# 7-seg_x_8-digRev2.net
KiCad netlist of a schematic drawn in EAGLE
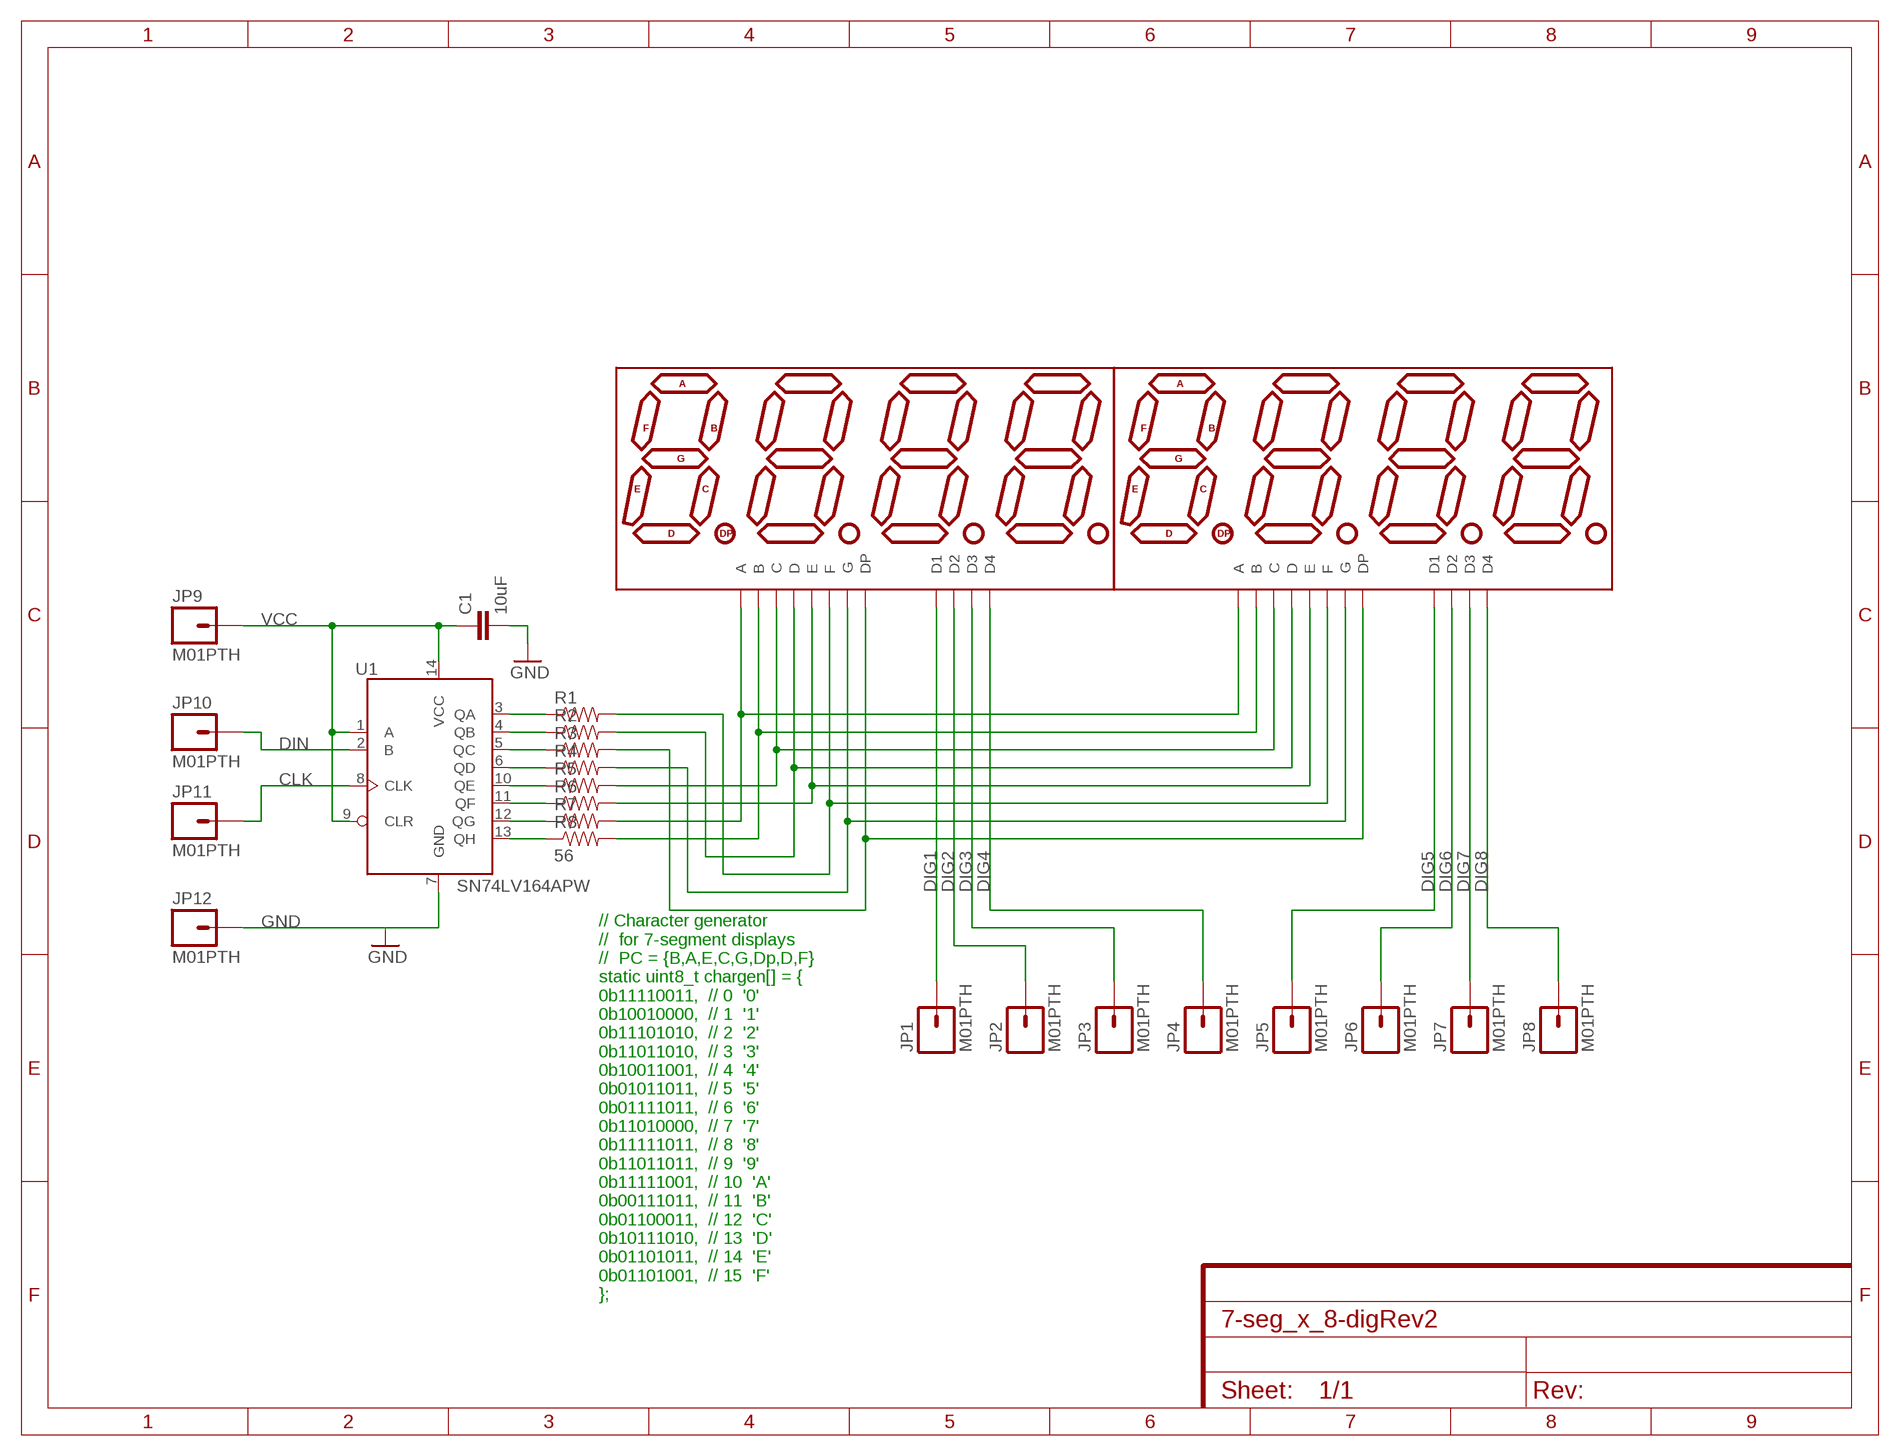
[diagram p0: schematic, sheet 1]

(export (version "E")
  (design (tool "Eeschema 10.0.6"))
  (components
    (comp (ref "C1")
      (value "10uF")
      (footprint "eagle-import:0805")
      (libsource (lib "eagle-import") (part "CAP0805"))
    )
    (comp (ref "FRAME1")
      (value "FRAME_LTR_CU_MARK")
      (footprint "eagle-import:FR-LTR-ON-PCB")
      (fields
        (field (name "CNAME") "C.Schnarel")
        (field (name "CREVISION") "Rev 2")
        (field (name "DESIGNER") "C.Schnarel")
      )
      (libsource (lib "eagle-import") (part "FRAME_LTR_CU_MARK"))
    )
    (comp (ref "JP1")
      (value "M01PTH")
      (footprint "eagle-import:1X01")
      (libsource (lib "eagle-import") (part "M01PTH"))
    )
    (comp (ref "JP2")
      (value "M01PTH")
      (footprint "eagle-import:1X01")
      (libsource (lib "eagle-import") (part "M01PTH"))
    )
    (comp (ref "JP3")
      (value "M01PTH")
      (footprint "eagle-import:1X01")
      (libsource (lib "eagle-import") (part "M01PTH"))
    )
    (comp (ref "JP4")
      (value "M01PTH")
      (footprint "eagle-import:1X01")
      (libsource (lib "eagle-import") (part "M01PTH"))
    )
    (comp (ref "JP5")
      (value "M01PTH")
      (footprint "eagle-import:1X01")
      (libsource (lib "eagle-import") (part "M01PTH"))
    )
    (comp (ref "JP6")
      (value "M01PTH")
      (footprint "eagle-import:1X01")
      (libsource (lib "eagle-import") (part "M01PTH"))
    )
    (comp (ref "JP7")
      (value "M01PTH")
      (footprint "eagle-import:1X01")
      (libsource (lib "eagle-import") (part "M01PTH"))
    )
    (comp (ref "JP8")
      (value "M01PTH")
      (footprint "eagle-import:1X01")
      (libsource (lib "eagle-import") (part "M01PTH"))
    )
    (comp (ref "JP9")
      (value "M01PTH")
      (footprint "eagle-import:1X01")
      (libsource (lib "eagle-import") (part "M01PTH"))
    )
    (comp (ref "JP10")
      (value "M01PTH")
      (footprint "eagle-import:1X01")
      (libsource (lib "eagle-import") (part "M01PTH"))
    )
    (comp (ref "JP11")
      (value "M01PTH")
      (footprint "eagle-import:1X01")
      (libsource (lib "eagle-import") (part "M01PTH"))
    )
    (comp (ref "JP12")
      (value "M01PTH")
      (footprint "eagle-import:1X01")
      (libsource (lib "eagle-import") (part "M01PTH"))
    )
    (comp (ref "R1")
      (value "RESISTOR0805-RES")
      (footprint "eagle-import:0805")
      (libsource (lib "eagle-import") (part "RESISTOR0805-RES"))
    )
    (comp (ref "R2")
      (value "RESISTOR0805-RES")
      (footprint "eagle-import:0805")
      (libsource (lib "eagle-import") (part "RESISTOR0805-RES"))
    )
    (comp (ref "R3")
      (value "RESISTOR0805-RES")
      (footprint "eagle-import:0805")
      (libsource (lib "eagle-import") (part "RESISTOR0805-RES"))
    )
    (comp (ref "R4")
      (value "RESISTOR0805-RES")
      (footprint "eagle-import:0805")
      (libsource (lib "eagle-import") (part "RESISTOR0805-RES"))
    )
    (comp (ref "R5")
      (value "RESISTOR0805-RES")
      (footprint "eagle-import:0805")
      (libsource (lib "eagle-import") (part "RESISTOR0805-RES"))
    )
    (comp (ref "R6")
      (value "RESISTOR0805-RES")
      (footprint "eagle-import:0805")
      (libsource (lib "eagle-import") (part "RESISTOR0805-RES"))
    )
    (comp (ref "R7")
      (value "RESISTOR0805-RES")
      (footprint "eagle-import:0805")
      (libsource (lib "eagle-import") (part "RESISTOR0805-RES"))
    )
    (comp (ref "R8")
      (value "56")
      (footprint "eagle-import:0805")
      (libsource (lib "eagle-import") (part "RESISTOR0805-RES"))
    )
    (comp (ref "U$1")
      (value "HP_DISPLAY")
      (footprint "eagle-import:DIL12")
      (libsource (lib "eagle-import") (part "HP_DISPLAY"))
    )
    (comp (ref "U$2")
      (value "HP_DISPLAY")
      (footprint "eagle-import:DIL12")
      (libsource (lib "eagle-import") (part "HP_DISPLAY"))
    )
    (comp (ref "U1")
      (value "SN74LV164APW")
      (footprint "eagle-import:TSSOP-14(TI)")
      (libsource (lib "eagle-import") (part "SN74LV164APW"))
    )
  )
  (nets
    (net (code "1") (name "/CLK") (class "Default")
      (node (ref "JP11") (pin "1") (pinfunction "1_1") (pintype "passive"))
      (node (ref "U1") (pin "8") (pinfunction "CLK_8") (pintype "input"))
    )
    (net (code "2") (name "/DIG1") (class "Default")
      (node (ref "JP1") (pin "1") (pinfunction "1_1") (pintype "passive"))
      (node (ref "U$1") (pin "1") (pinfunction "D1_1") (pintype "bidirectional"))
    )
    (net (code "3") (name "/DIG2") (class "Default")
      (node (ref "JP2") (pin "1") (pinfunction "1_1") (pintype "passive"))
      (node (ref "U$1") (pin "10") (pinfunction "D2_10") (pintype "bidirectional"))
    )
    (net (code "4") (name "/DIG3") (class "Default")
      (node (ref "JP3") (pin "1") (pinfunction "1_1") (pintype "passive"))
      (node (ref "U$1") (pin "4") (pinfunction "D3_4") (pintype "bidirectional"))
    )
    (net (code "5") (name "/DIG4") (class "Default")
      (node (ref "JP4") (pin "1") (pinfunction "1_1") (pintype "passive"))
      (node (ref "U$1") (pin "6") (pinfunction "D4_6") (pintype "bidirectional"))
    )
    (net (code "6") (name "/DIG5") (class "Default")
      (node (ref "JP5") (pin "1") (pinfunction "1_1") (pintype "passive"))
      (node (ref "U$2") (pin "1") (pinfunction "D1_1") (pintype "bidirectional"))
    )
    (net (code "7") (name "/DIG6") (class "Default")
      (node (ref "JP6") (pin "1") (pinfunction "1_1") (pintype "passive"))
      (node (ref "U$2") (pin "10") (pinfunction "D2_10") (pintype "bidirectional"))
    )
    (net (code "8") (name "/DIG7") (class "Default")
      (node (ref "JP7") (pin "1") (pinfunction "1_1") (pintype "passive"))
      (node (ref "U$2") (pin "4") (pinfunction "D3_4") (pintype "bidirectional"))
    )
    (net (code "9") (name "/DIG8") (class "Default")
      (node (ref "JP8") (pin "1") (pinfunction "1_1") (pintype "passive"))
      (node (ref "U$2") (pin "6") (pinfunction "D4_6") (pintype "bidirectional"))
    )
    (net (code "10") (name "/DIN") (class "Default")
      (node (ref "JP10") (pin "1") (pinfunction "1_1") (pintype "passive"))
      (node (ref "U1") (pin "2") (pinfunction "B_2") (pintype "input"))
    )
    (net (code "11") (name "/VCC") (class "Default")
      (node (ref "C1") (pin "1") (pinfunction "1_1") (pintype "passive"))
      (node (ref "JP9") (pin "1") (pinfunction "1_1") (pintype "passive"))
      (node (ref "U1") (pin "1") (pinfunction "A_1") (pintype "bidirectional"))
      (node (ref "U1") (pin "14") (pinfunction "VCC_14") (pintype "power_in"))
      (node (ref "U1") (pin "9") (pinfunction "CLR_9") (pintype "bidirectional"))
    )
    (net (code "12") (name "GND") (class "Default")
      (node (ref "C1") (pin "2") (pinfunction "2_2") (pintype "passive"))
      (node (ref "JP12") (pin "1") (pinfunction "1_1") (pintype "passive"))
      (node (ref "U1") (pin "7") (pinfunction "GND_7") (pintype "power_in"))
    )
    (net (code "13") (name "Net-(U$1-A)") (class "Default")
      (node (ref "R7") (pin "2") (pinfunction "2_2") (pintype "passive"))
      (node (ref "U$1") (pin "12") (pinfunction "A_12") (pintype "bidirectional"))
      (node (ref "U$2") (pin "12") (pinfunction "A_12") (pintype "bidirectional"))
    )
    (net (code "14") (name "Net-(U$1-B)") (class "Default")
      (node (ref "R8") (pin "2") (pinfunction "2_2") (pintype "passive"))
      (node (ref "U$1") (pin "11") (pinfunction "B_11") (pintype "bidirectional"))
      (node (ref "U$2") (pin "11") (pinfunction "B_11") (pintype "bidirectional"))
    )
    (net (code "15") (name "Net-(U$1-C)") (class "Default")
      (node (ref "R5") (pin "2") (pinfunction "2_2") (pintype "passive"))
      (node (ref "U$1") (pin "3") (pinfunction "C_3") (pintype "bidirectional"))
      (node (ref "U$2") (pin "3") (pinfunction "C_3") (pintype "bidirectional"))
    )
    (net (code "16") (name "Net-(U$1-D)") (class "Default")
      (node (ref "R2") (pin "2") (pinfunction "2_2") (pintype "passive"))
      (node (ref "U$1") (pin "8") (pinfunction "D_8") (pintype "bidirectional"))
      (node (ref "U$2") (pin "8") (pinfunction "D_8") (pintype "bidirectional"))
    )
    (net (code "17") (name "Net-(U$1-DP)") (class "Default")
      (node (ref "R3") (pin "2") (pinfunction "2_2") (pintype "passive"))
      (node (ref "U$1") (pin "5") (pinfunction "DP_5") (pintype "bidirectional"))
      (node (ref "U$2") (pin "5") (pinfunction "DP_5") (pintype "bidirectional"))
    )
    (net (code "18") (name "Net-(U$1-E)") (class "Default")
      (node (ref "R6") (pin "2") (pinfunction "2_2") (pintype "passive"))
      (node (ref "U$1") (pin "2") (pinfunction "E_2") (pintype "bidirectional"))
      (node (ref "U$2") (pin "2") (pinfunction "E_2") (pintype "bidirectional"))
    )
    (net (code "19") (name "Net-(U$1-F)") (class "Default")
      (node (ref "R1") (pin "2") (pinfunction "2_2") (pintype "passive"))
      (node (ref "U$1") (pin "9") (pinfunction "F_9") (pintype "bidirectional"))
      (node (ref "U$2") (pin "9") (pinfunction "F_9") (pintype "bidirectional"))
    )
    (net (code "20") (name "Net-(U$1-G)") (class "Default")
      (node (ref "R4") (pin "2") (pinfunction "2_2") (pintype "passive"))
      (node (ref "U$1") (pin "7") (pinfunction "G_7") (pintype "bidirectional"))
      (node (ref "U$2") (pin "7") (pinfunction "G_7") (pintype "bidirectional"))
    )
    (net (code "21") (name "Net-(U1-QA)") (class "Default")
      (node (ref "R1") (pin "1") (pinfunction "1_1") (pintype "passive"))
      (node (ref "U1") (pin "3") (pinfunction "QA_3") (pintype "bidirectional"))
    )
    (net (code "22") (name "Net-(U1-QB)") (class "Default")
      (node (ref "R2") (pin "1") (pinfunction "1_1") (pintype "passive"))
      (node (ref "U1") (pin "4") (pinfunction "QB_4") (pintype "bidirectional"))
    )
    (net (code "23") (name "Net-(U1-QC)") (class "Default")
      (node (ref "R3") (pin "1") (pinfunction "1_1") (pintype "passive"))
      (node (ref "U1") (pin "5") (pinfunction "QC_5") (pintype "bidirectional"))
    )
    (net (code "24") (name "Net-(U1-QD)") (class "Default")
      (node (ref "R4") (pin "1") (pinfunction "1_1") (pintype "passive"))
      (node (ref "U1") (pin "6") (pinfunction "QD_6") (pintype "bidirectional"))
    )
    (net (code "25") (name "Net-(U1-QE)") (class "Default")
      (node (ref "R5") (pin "1") (pinfunction "1_1") (pintype "passive"))
      (node (ref "U1") (pin "10") (pinfunction "QE_10") (pintype "bidirectional"))
    )
    (net (code "26") (name "Net-(U1-QF)") (class "Default")
      (node (ref "R6") (pin "1") (pinfunction "1_1") (pintype "passive"))
      (node (ref "U1") (pin "11") (pinfunction "QF_11") (pintype "bidirectional"))
    )
    (net (code "27") (name "Net-(U1-QG)") (class "Default")
      (node (ref "R7") (pin "1") (pinfunction "1_1") (pintype "passive"))
      (node (ref "U1") (pin "12") (pinfunction "QG_12") (pintype "bidirectional"))
    )
    (net (code "28") (name "Net-(U1-QH)") (class "Default")
      (node (ref "R8") (pin "1") (pinfunction "1_1") (pintype "passive"))
      (node (ref "U1") (pin "13") (pinfunction "QH_13") (pintype "bidirectional"))
    )
  )
)
